# golia.net
KiCad netlist of a schematic drawn in EAGLE
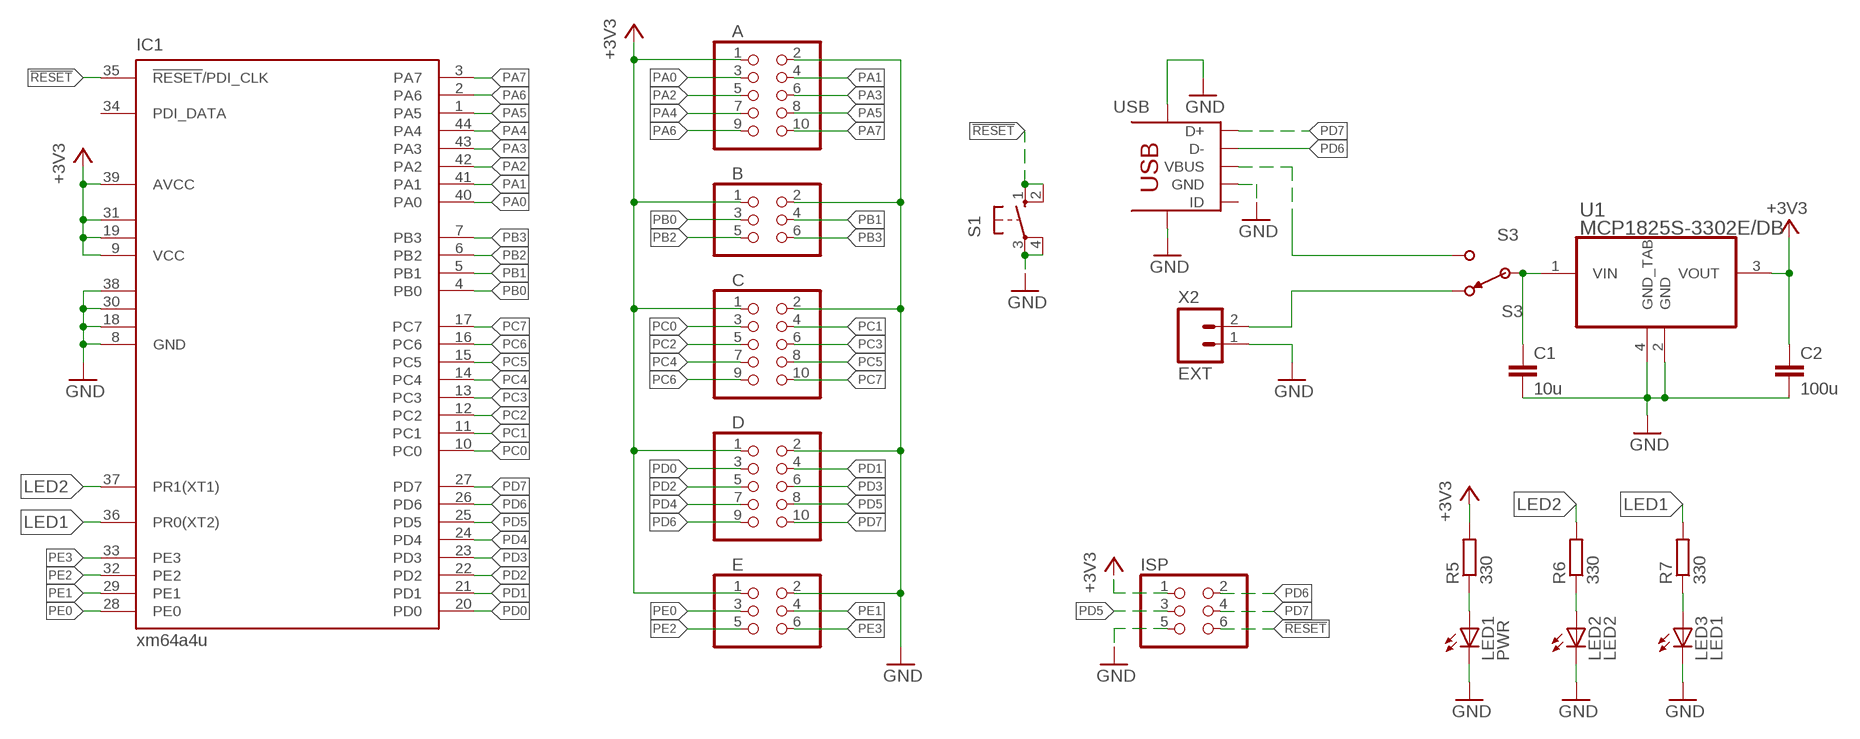
[diagram p0: schematic, sheet 1]

(export (version "E")
  (design (tool "Eeschema 10.0.6"))
  (components
    (comp (ref "A")
      (value "PINHD-2X5")
      (footprint "eagle-import:2X05")
      (libsource (lib "eagle-import") (part "PINHD-2X5"))
    )
    (comp (ref "B")
      (value "PINHD-2X3")
      (footprint "eagle-import:2X03")
      (libsource (lib "eagle-import") (part "PINHD-2X3"))
    )
    (comp (ref "C")
      (value "PINHD-2X5")
      (footprint "eagle-import:2X05")
      (libsource (lib "eagle-import") (part "PINHD-2X5"))
    )
    (comp (ref "C1")
      (value "10u")
      (footprint "eagle-import:C0603")
      (libsource (lib "eagle-import") (part "C0603"))
    )
    (comp (ref "C2")
      (value "100u")
      (footprint "eagle-import:C1206")
      (libsource (lib "eagle-import") (part "C-EUC1206"))
    )
    (comp (ref "D")
      (value "PINHD-2X5")
      (footprint "eagle-import:2X05")
      (libsource (lib "eagle-import") (part "PINHD-2X5"))
    )
    (comp (ref "E")
      (value "PINHD-2X3")
      (footprint "eagle-import:2X03")
      (libsource (lib "eagle-import") (part "PINHD-2X3"))
    )
    (comp (ref "IC1")
      (value "xm64a4u")
      (footprint "eagle-import:TQFP44")
      (libsource (lib "eagle-import") (part "XMEGA16A4A"))
    )
    (comp (ref "ISP")
      (value "PINHD-2X3")
      (footprint "eagle-import:2X03")
      (libsource (lib "eagle-import") (part "PINHD-2X3"))
    )
    (comp (ref "LED1")
      (value "PWR")
      (footprint "eagle-import:CHIP-LED0805")
      (libsource (lib "eagle-import") (part "LEDCHIP-LED0805"))
    )
    (comp (ref "LED2")
      (value "LED2")
      (footprint "eagle-import:CHIP-LED0805")
      (libsource (lib "eagle-import") (part "LEDCHIP-LED0805"))
    )
    (comp (ref "LED3")
      (value "LED1")
      (footprint "eagle-import:CHIP-LED0805")
      (libsource (lib "eagle-import") (part "LEDCHIP-LED0805"))
    )
    (comp (ref "R5")
      (value "330")
      (footprint "eagle-import:R0603")
      (libsource (lib "eagle-import") (part "R-EU_R0603"))
    )
    (comp (ref "R6")
      (value "330")
      (footprint "eagle-import:R0603")
      (libsource (lib "eagle-import") (part "R-EU_R0603"))
    )
    (comp (ref "R7")
      (value "330")
      (footprint "eagle-import:R0603")
      (libsource (lib "eagle-import") (part "R-EU_R0603"))
    )
    (comp (ref "S1")
      (value "10-XX")
      (footprint "eagle-import:B3F-10XX")
      (fields (field (name "MPN") "B3F-1000"))
      (libsource (lib "eagle-import") (part "10-XX"))
    )
    (comp (ref "S3")
      (value "S3")
      (footprint "eagle-import:EG-1218")
      (libsource (lib "eagle-import") (part "SPDTEG-1218"))
    )
    (comp (ref "U1")
      (value "MCP1825S-3302E/DB")
      (footprint "eagle-import:SOT230P700X180-4N")
      (libsource (lib "eagle-import") (part "MCP1825S-3302E/DB"))
    )
    (comp (ref "USB")
      (value "USB-MINIB-PTH")
      (footprint "eagle-import:USB-MINIB-PTH")
      (libsource (lib "eagle-import") (part "USB-MINIB-PTH"))
    )
    (comp (ref "X2")
      (value "EXT")
      (footprint "eagle-import:JST-2-2MM-PTH-VERT-LOCK")
      (libsource (lib "eagle-import") (part "JST-22MM-PTH-VERT-LOCK"))
    )
  )
  (nets
    (net (code "1") (name "+3V3") (class "Default")
      (node (ref "A") (pin "1") (pinfunction "1_1") (pintype "passive"))
      (node (ref "B") (pin "1") (pinfunction "1_1") (pintype "passive"))
      (node (ref "C") (pin "1") (pinfunction "1_1") (pintype "passive"))
      (node (ref "C2") (pin "1") (pinfunction "1_1") (pintype "passive"))
      (node (ref "D") (pin "1") (pinfunction "1_1") (pintype "passive"))
      (node (ref "E") (pin "1") (pinfunction "1_1") (pintype "passive"))
      (node (ref "IC1") (pin "19") (pinfunction "VCC1_19") (pintype "power_in"))
      (node (ref "IC1") (pin "31") (pinfunction "VCC2_31") (pintype "power_in"))
      (node (ref "IC1") (pin "39") (pinfunction "AVCC_39") (pintype "power_in"))
      (node (ref "IC1") (pin "9") (pinfunction "VCC_9") (pintype "power_in"))
      (node (ref "ISP") (pin "1") (pinfunction "1_1") (pintype "passive"))
      (node (ref "R5") (pin "2") (pinfunction "2_2") (pintype "passive"))
      (node (ref "U1") (pin "3") (pinfunction "VOUT_3") (pintype "power_in"))
    )
    (net (code "2") (name "/~{RESET}") (class "Default")
      (node (ref "IC1") (pin "35") (pinfunction "~{RESET}/PDI_CLK_35") (pintype "bidirectional"))
      (node (ref "ISP") (pin "6") (pinfunction "6_6") (pintype "passive"))
      (node (ref "S1") (pin "1") (pinfunction "S_1") (pintype "passive"))
      (node (ref "S1") (pin "2") (pinfunction "S1_2") (pintype "passive"))
    )
    (net (code "3") (name "GND") (class "Default")
      (node (ref "A") (pin "2") (pinfunction "2_2") (pintype "passive"))
      (node (ref "B") (pin "2") (pinfunction "2_2") (pintype "passive"))
      (node (ref "C") (pin "2") (pinfunction "2_2") (pintype "passive"))
      (node (ref "C1") (pin "2") (pinfunction "2_2") (pintype "passive"))
      (node (ref "C2") (pin "2") (pinfunction "2_2") (pintype "passive"))
      (node (ref "D") (pin "2") (pinfunction "2_2") (pintype "passive"))
      (node (ref "E") (pin "2") (pinfunction "2_2") (pintype "passive"))
      (node (ref "IC1") (pin "18") (pinfunction "GND1_18") (pintype "power_in"))
      (node (ref "IC1") (pin "30") (pinfunction "GND2_30") (pintype "power_in"))
      (node (ref "IC1") (pin "38") (pinfunction "GND3_38") (pintype "power_in"))
      (node (ref "IC1") (pin "8") (pinfunction "GND_8") (pintype "power_in"))
      (node (ref "ISP") (pin "5") (pinfunction "5_5") (pintype "passive"))
      (node (ref "LED1") (pin "C") (pinfunction "C_C") (pintype "passive"))
      (node (ref "LED2") (pin "C") (pinfunction "C_C") (pintype "passive"))
      (node (ref "LED3") (pin "C") (pinfunction "C_C") (pintype "passive"))
      (node (ref "S1") (pin "3") (pinfunction "P_3") (pintype "passive"))
      (node (ref "S1") (pin "4") (pinfunction "P1_4") (pintype "passive"))
      (node (ref "U1") (pin "2") (pinfunction "GND_2") (pintype "power_in"))
      (node (ref "U1") (pin "4") (pinfunction "GND_TAB_4") (pintype "power_in"))
      (node (ref "USB") (pin "GND") (pinfunction "GND_GND") (pintype "bidirectional"))
      (node (ref "USB") (pin "P$6") (pinfunction "SHD1_P$6") (pintype "bidirectional"))
      (node (ref "USB") (pin "P$7") (pinfunction "SHD2_P$7") (pintype "bidirectional"))
      (node (ref "X2") (pin "1") (pinfunction "1_1") (pintype "passive"))
    )
    (net (code "4") (name "LED1") (class "Default")
      (node (ref "IC1") (pin "36") (pinfunction "PR0(XT2)_36") (pintype "bidirectional"))
      (node (ref "R7") (pin "2") (pinfunction "2_2") (pintype "passive"))
    )
    (net (code "5") (name "LED2") (class "Default")
      (node (ref "IC1") (pin "37") (pinfunction "PR1(XT1)_37") (pintype "bidirectional"))
      (node (ref "R6") (pin "2") (pinfunction "2_2") (pintype "passive"))
    )
    (net (code "6") (name "Net-(LED1-PadA)") (class "Default")
      (node (ref "LED1") (pin "A") (pinfunction "A_A") (pintype "passive"))
      (node (ref "R5") (pin "1") (pinfunction "1_1") (pintype "passive"))
    )
    (net (code "7") (name "Net-(LED2-PadA)") (class "Default")
      (node (ref "LED2") (pin "A") (pinfunction "A_A") (pintype "passive"))
      (node (ref "R6") (pin "1") (pinfunction "1_1") (pintype "passive"))
    )
    (net (code "8") (name "Net-(LED3-PadA)") (class "Default")
      (node (ref "LED3") (pin "A") (pinfunction "A_A") (pintype "passive"))
      (node (ref "R7") (pin "1") (pinfunction "1_1") (pintype "passive"))
    )
    (net (code "9") (name "Net-(S3-2)") (class "Default")
      (node (ref "S3") (pin "3") (pinfunction "2_3") (pintype "passive"))
      (node (ref "USB") (pin "VBUS") (pinfunction "VBUS_VBUS") (pintype "bidirectional"))
    )
    (net (code "10") (name "Net-(S3-C)") (class "Default")
      (node (ref "C1") (pin "1") (pinfunction "1_1") (pintype "passive"))
      (node (ref "S3") (pin "2") (pinfunction "C_2") (pintype "passive"))
      (node (ref "U1") (pin "1") (pinfunction "VIN_1") (pintype "power_in"))
    )
    (net (code "11") (name "Net-(S3-Pad1)") (class "Default")
      (node (ref "S3") (pin "1") (pinfunction "1_1") (pintype "passive"))
      (node (ref "X2") (pin "2") (pinfunction "2_2") (pintype "passive"))
    )
    (net (code "12") (name "PA0") (class "Default")
      (node (ref "A") (pin "3") (pinfunction "3_3") (pintype "passive"))
      (node (ref "IC1") (pin "40") (pinfunction "PA0_40") (pintype "bidirectional"))
    )
    (net (code "13") (name "PA1") (class "Default")
      (node (ref "A") (pin "4") (pinfunction "4_4") (pintype "passive"))
      (node (ref "IC1") (pin "41") (pinfunction "PA1_41") (pintype "bidirectional"))
    )
    (net (code "14") (name "PA2") (class "Default")
      (node (ref "A") (pin "5") (pinfunction "5_5") (pintype "passive"))
      (node (ref "IC1") (pin "42") (pinfunction "PA2_42") (pintype "bidirectional"))
    )
    (net (code "15") (name "PA3") (class "Default")
      (node (ref "A") (pin "6") (pinfunction "6_6") (pintype "passive"))
      (node (ref "IC1") (pin "43") (pinfunction "PA3_43") (pintype "bidirectional"))
    )
    (net (code "16") (name "PA4") (class "Default")
      (node (ref "A") (pin "7") (pinfunction "7_7") (pintype "passive"))
      (node (ref "IC1") (pin "44") (pinfunction "PA4_44") (pintype "bidirectional"))
    )
    (net (code "17") (name "PA5") (class "Default")
      (node (ref "A") (pin "8") (pinfunction "8_8") (pintype "passive"))
      (node (ref "IC1") (pin "1") (pinfunction "PA5_1") (pintype "bidirectional"))
    )
    (net (code "18") (name "PA6") (class "Default")
      (node (ref "A") (pin "9") (pinfunction "9_9") (pintype "passive"))
      (node (ref "IC1") (pin "2") (pinfunction "PA6_2") (pintype "bidirectional"))
    )
    (net (code "19") (name "PA7") (class "Default")
      (node (ref "A") (pin "10") (pinfunction "10_10") (pintype "passive"))
      (node (ref "IC1") (pin "3") (pinfunction "PA7_3") (pintype "bidirectional"))
    )
    (net (code "20") (name "PB0") (class "Default")
      (node (ref "B") (pin "3") (pinfunction "3_3") (pintype "passive"))
      (node (ref "IC1") (pin "4") (pinfunction "PB0_4") (pintype "bidirectional"))
    )
    (net (code "21") (name "PB1") (class "Default")
      (node (ref "B") (pin "4") (pinfunction "4_4") (pintype "passive"))
      (node (ref "IC1") (pin "5") (pinfunction "PB1_5") (pintype "bidirectional"))
    )
    (net (code "22") (name "PB2") (class "Default")
      (node (ref "B") (pin "5") (pinfunction "5_5") (pintype "passive"))
      (node (ref "IC1") (pin "6") (pinfunction "PB2_6") (pintype "bidirectional"))
    )
    (net (code "23") (name "PB3") (class "Default")
      (node (ref "B") (pin "6") (pinfunction "6_6") (pintype "passive"))
      (node (ref "IC1") (pin "7") (pinfunction "PB3_7") (pintype "bidirectional"))
    )
    (net (code "24") (name "PC0") (class "Default")
      (node (ref "C") (pin "3") (pinfunction "3_3") (pintype "passive"))
      (node (ref "IC1") (pin "10") (pinfunction "PC0_10") (pintype "bidirectional"))
    )
    (net (code "25") (name "PC1") (class "Default")
      (node (ref "C") (pin "4") (pinfunction "4_4") (pintype "passive"))
      (node (ref "IC1") (pin "11") (pinfunction "PC1_11") (pintype "bidirectional"))
    )
    (net (code "26") (name "PC2") (class "Default")
      (node (ref "C") (pin "5") (pinfunction "5_5") (pintype "passive"))
      (node (ref "IC1") (pin "12") (pinfunction "PC2_12") (pintype "bidirectional"))
    )
    (net (code "27") (name "PC3") (class "Default")
      (node (ref "C") (pin "6") (pinfunction "6_6") (pintype "passive"))
      (node (ref "IC1") (pin "13") (pinfunction "PC3_13") (pintype "bidirectional"))
    )
    (net (code "28") (name "PC4") (class "Default")
      (node (ref "C") (pin "7") (pinfunction "7_7") (pintype "passive"))
      (node (ref "IC1") (pin "14") (pinfunction "PC4_14") (pintype "bidirectional"))
    )
    (net (code "29") (name "PC5") (class "Default")
      (node (ref "C") (pin "8") (pinfunction "8_8") (pintype "passive"))
      (node (ref "IC1") (pin "15") (pinfunction "PC5_15") (pintype "bidirectional"))
    )
    (net (code "30") (name "PC6") (class "Default")
      (node (ref "C") (pin "9") (pinfunction "9_9") (pintype "passive"))
      (node (ref "IC1") (pin "16") (pinfunction "PC6_16") (pintype "bidirectional"))
    )
    (net (code "31") (name "PC7") (class "Default")
      (node (ref "C") (pin "10") (pinfunction "10_10") (pintype "passive"))
      (node (ref "IC1") (pin "17") (pinfunction "PC7_17") (pintype "bidirectional"))
    )
    (net (code "32") (name "PD0") (class "Default")
      (node (ref "D") (pin "3") (pinfunction "3_3") (pintype "passive"))
      (node (ref "IC1") (pin "20") (pinfunction "PD0_20") (pintype "bidirectional"))
    )
    (net (code "33") (name "PD1") (class "Default")
      (node (ref "D") (pin "4") (pinfunction "4_4") (pintype "passive"))
      (node (ref "IC1") (pin "21") (pinfunction "PD1_21") (pintype "bidirectional"))
    )
    (net (code "34") (name "PD2") (class "Default")
      (node (ref "D") (pin "5") (pinfunction "5_5") (pintype "passive"))
      (node (ref "IC1") (pin "22") (pinfunction "PD2_22") (pintype "bidirectional"))
    )
    (net (code "35") (name "PD3") (class "Default")
      (node (ref "D") (pin "6") (pinfunction "6_6") (pintype "passive"))
      (node (ref "IC1") (pin "23") (pinfunction "PD3_23") (pintype "bidirectional"))
    )
    (net (code "36") (name "PD4") (class "Default")
      (node (ref "D") (pin "7") (pinfunction "7_7") (pintype "passive"))
      (node (ref "IC1") (pin "24") (pinfunction "PD4_24") (pintype "bidirectional"))
    )
    (net (code "37") (name "PD5") (class "Default")
      (node (ref "D") (pin "8") (pinfunction "8_8") (pintype "passive"))
      (node (ref "IC1") (pin "25") (pinfunction "PD5_25") (pintype "bidirectional"))
      (node (ref "ISP") (pin "3") (pinfunction "3_3") (pintype "passive"))
    )
    (net (code "38") (name "PD6") (class "Default")
      (node (ref "D") (pin "9") (pinfunction "9_9") (pintype "passive"))
      (node (ref "IC1") (pin "26") (pinfunction "PD6_26") (pintype "bidirectional"))
      (node (ref "ISP") (pin "2") (pinfunction "2_2") (pintype "passive"))
      (node (ref "USB") (pin "D-") (pinfunction "D-_D-") (pintype "bidirectional"))
    )
    (net (code "39") (name "PD7") (class "Default")
      (node (ref "D") (pin "10") (pinfunction "10_10") (pintype "passive"))
      (node (ref "IC1") (pin "27") (pinfunction "PD7_27") (pintype "bidirectional"))
      (node (ref "ISP") (pin "4") (pinfunction "4_4") (pintype "passive"))
      (node (ref "USB") (pin "D+") (pinfunction "D+_D+") (pintype "bidirectional"))
    )
    (net (code "40") (name "PE0") (class "Default")
      (node (ref "E") (pin "3") (pinfunction "3_3") (pintype "passive"))
      (node (ref "IC1") (pin "28") (pinfunction "PE0_28") (pintype "bidirectional"))
    )
    (net (code "41") (name "PE1") (class "Default")
      (node (ref "E") (pin "4") (pinfunction "4_4") (pintype "passive"))
      (node (ref "IC1") (pin "29") (pinfunction "PE1_29") (pintype "bidirectional"))
    )
    (net (code "42") (name "PE2") (class "Default")
      (node (ref "E") (pin "5") (pinfunction "5_5") (pintype "passive"))
      (node (ref "IC1") (pin "32") (pinfunction "PE2_32") (pintype "bidirectional"))
    )
    (net (code "43") (name "PE3") (class "Default")
      (node (ref "E") (pin "6") (pinfunction "6_6") (pintype "passive"))
      (node (ref "IC1") (pin "33") (pinfunction "PE3_33") (pintype "bidirectional"))
    )
    (net (code "44") (name "unconnected-(IC1-PDI_DATA-Pad34)") (class "Default")
      (node (ref "IC1") (pin "34") (pinfunction "PDI_DATA_34") (pintype "bidirectional"))
    )
    (net (code "45") (name "unconnected-(USB-PadID)") (class "Default")
      (node (ref "USB") (pin "ID") (pinfunction "ID_ID") (pintype "bidirectional"))
    )
  )
)
